# HW1_Justin_Ngo_u0453732_MotorPCB.net
KiCad netlist of a schematic drawn in EAGLE
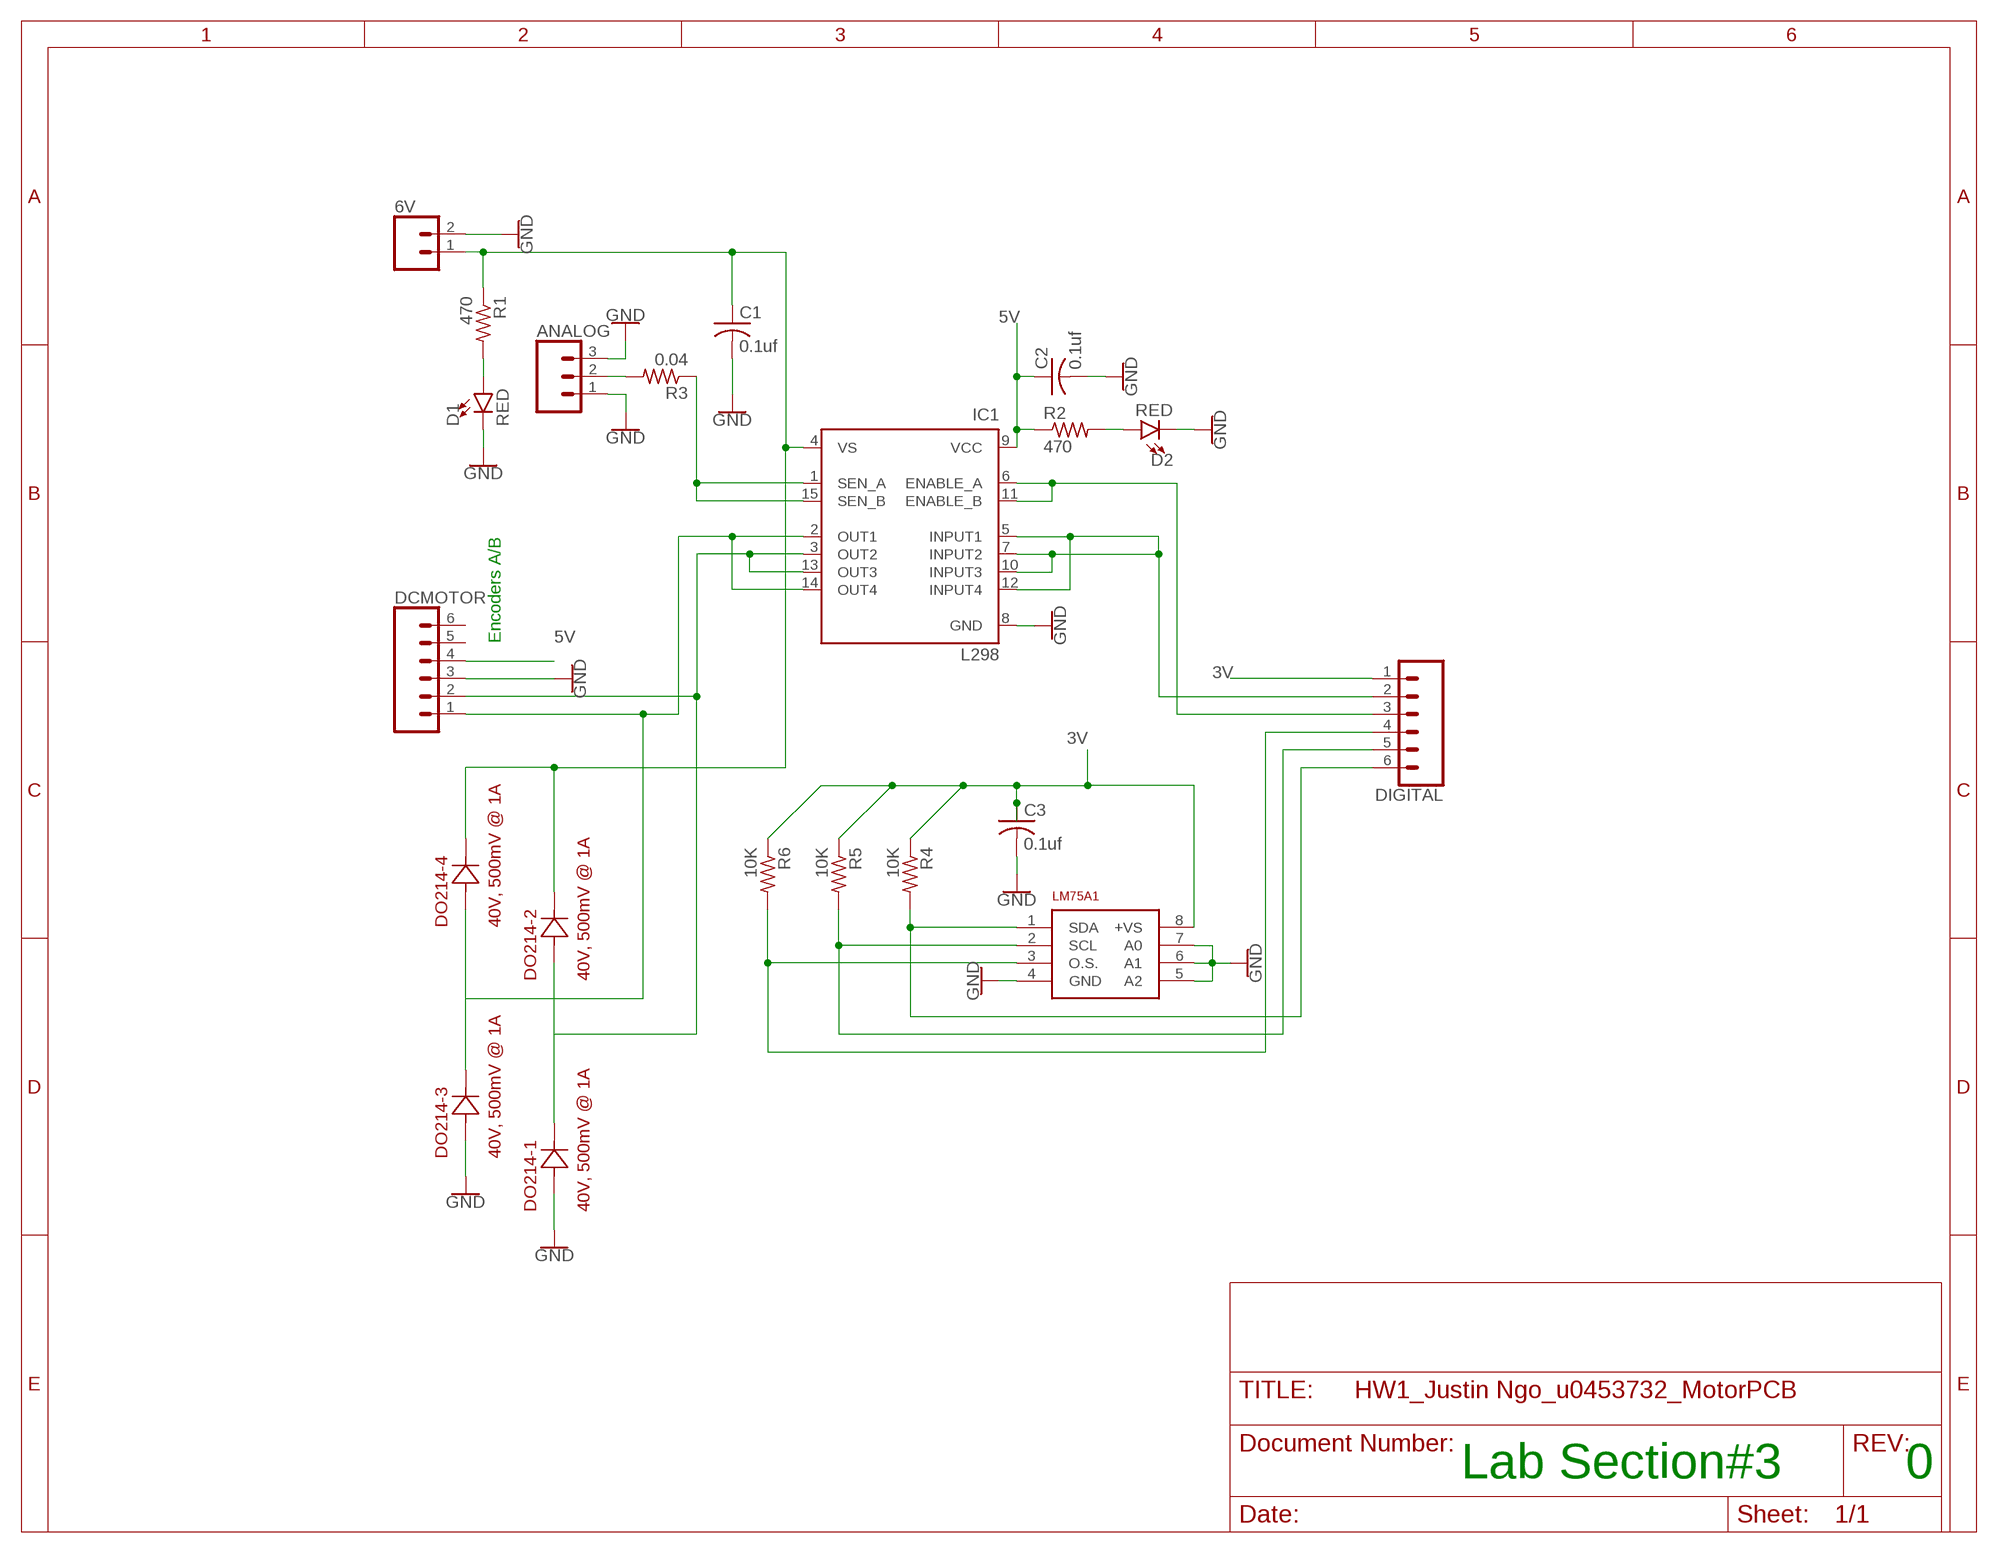
[diagram p0: schematic, sheet 1]

(export (version "E")
  (design (tool "Eeschema 10.0.6"))
  (components
    (comp (ref "6V")
      (value "CONN_025MM")
      (footprint "eagle-import:SCREWTERMINAL-5MM-2")
      (libsource (lib "eagle-import") (part "CONN_025MM"))
    )
    (comp (ref "ANALOG")
      (value "CONN_03")
      (footprint "eagle-import:1X03")
      (libsource (lib "eagle-import") (part "CONN_03"))
    )
    (comp (ref "C1")
      (value "0.1uf")
      (footprint "eagle-import:C1206")
      (libsource (lib "eagle-import") (part "C-USC1206"))
    )
    (comp (ref "C2")
      (value "0.1uf")
      (footprint "eagle-import:C1206")
      (libsource (lib "eagle-import") (part "C-USC1206"))
    )
    (comp (ref "C3")
      (value "0.1uf")
      (footprint "eagle-import:C1206")
      (libsource (lib "eagle-import") (part "C-USC1206"))
    )
    (comp (ref "D1")
      (value "RED")
      (footprint "eagle-import:LED-1206")
      (libsource (lib "eagle-import") (part "LED-RED1206"))
    )
    (comp (ref "D2")
      (value "RED")
      (footprint "eagle-import:LED-1206")
      (libsource (lib "eagle-import") (part "LED-RED1206"))
    )
    (comp (ref "DCMOTOR")
      (value "CONN_06LOCK_LONGPADS")
      (footprint "eagle-import:1X06_LOCK_LONGPADS")
      (libsource (lib "eagle-import") (part "CONN_06LOCK_LONGPADS"))
    )
    (comp (ref "DIGITAL")
      (value "CONN_06LOCK_LONGPADS")
      (footprint "eagle-import:1X06_LOCK_LONGPADS")
      (libsource (lib "eagle-import") (part "CONN_06LOCK_LONGPADS"))
    )
    (comp (ref "DO214-1")
      (value "40V, 500mV @ 1A")
      (footprint "eagle-import:DIODE_DO214AC")
      (fields
        (field (name "MANUFACTURER_PART_NUMBER") "SS14")
        (field (name "RSPARTNUMBER") "4470352")
        (field (name "COPYRIGHT") "Copyright C 2015 Accelerated Designs. All rights reserved")
      )
      (libsource (lib "eagle-import") (part "SS14"))
    )
    (comp (ref "DO214-2")
      (value "40V, 500mV @ 1A")
      (footprint "eagle-import:DIODE_DO214AC")
      (fields
        (field (name "MANUFACTURER_PART_NUMBER") "SS14")
        (field (name "RSPARTNUMBER") "4470352")
        (field (name "COPYRIGHT") "Copyright C 2015 Accelerated Designs. All rights reserved")
      )
      (libsource (lib "eagle-import") (part "SS14"))
    )
    (comp (ref "DO214-3")
      (value "40V, 500mV @ 1A")
      (footprint "eagle-import:DIODE_DO214AC")
      (fields
        (field (name "MANUFACTURER_PART_NUMBER") "SS14")
        (field (name "RSPARTNUMBER") "4470352")
        (field (name "COPYRIGHT") "Copyright C 2015 Accelerated Designs. All rights reserved")
      )
      (libsource (lib "eagle-import") (part "SS14"))
    )
    (comp (ref "DO214-4")
      (value "40V, 500mV @ 1A")
      (footprint "eagle-import:DIODE_DO214AC")
      (fields
        (field (name "MANUFACTURER_PART_NUMBER") "SS14")
        (field (name "RSPARTNUMBER") "4470352")
        (field (name "COPYRIGHT") "Copyright C 2015 Accelerated Designs. All rights reserved")
      )
      (libsource (lib "eagle-import") (part "SS14"))
    )
    (comp (ref "IC1")
      (value "L298")
      (footprint "eagle-import:MULTIWATT-15")
      (fields (field (name "MPN") "L298N"))
      (libsource (lib "eagle-import") (part "L298"))
    )
    (comp (ref "LM75A1")
      (value "TI-LM75A")
      (footprint "eagle-import:TI-LM75A")
      (libsource (lib "eagle-import") (part "TI-LM75A"))
    )
    (comp (ref "R1")
      (value "470")
      (footprint "eagle-import:R1206")
      (libsource (lib "eagle-import") (part "R-US_R1206"))
    )
    (comp (ref "R2")
      (value "470")
      (footprint "eagle-import:R1206")
      (libsource (lib "eagle-import") (part "R-US_R1206"))
    )
    (comp (ref "R3")
      (value "0.04")
      (footprint "eagle-import:R1206")
      (libsource (lib "eagle-import") (part "R-US_R1206"))
    )
    (comp (ref "R4")
      (value "10K")
      (footprint "eagle-import:R1206")
      (libsource (lib "eagle-import") (part "R-US_R1206"))
    )
    (comp (ref "R5")
      (value "10K")
      (footprint "eagle-import:R1206")
      (libsource (lib "eagle-import") (part "R-US_R1206"))
    )
    (comp (ref "R6")
      (value "10K")
      (footprint "eagle-import:R1206")
      (libsource (lib "eagle-import") (part "R-US_R1206"))
    )
  )
  (nets
    (net (code "1") (name "/3V") (class "Default")
      (node (ref "C3") (pin "1") (pinfunction "1_1") (pintype "passive"))
      (node (ref "DIGITAL") (pin "1") (pinfunction "1_1") (pintype "passive"))
      (node (ref "LM75A1") (pin "8") (pinfunction "+VS_8") (pintype "bidirectional"))
      (node (ref "R4") (pin "1") (pinfunction "1_1") (pintype "passive"))
      (node (ref "R5") (pin "1") (pinfunction "1_1") (pintype "passive"))
      (node (ref "R6") (pin "1") (pinfunction "1_1") (pintype "passive"))
    )
    (net (code "2") (name "/5V") (class "Default")
      (node (ref "C2") (pin "1") (pinfunction "1_1") (pintype "passive"))
      (node (ref "DCMOTOR") (pin "4") (pinfunction "4_4") (pintype "passive"))
      (node (ref "IC1") (pin "9") (pinfunction "VCC_9") (pintype "power_in"))
      (node (ref "R2") (pin "1") (pinfunction "1_1") (pintype "passive"))
    )
    (net (code "3") (name "GND") (class "Default")
      (node (ref "6V") (pin "2") (pinfunction "2_2") (pintype "passive"))
      (node (ref "ANALOG") (pin "1") (pinfunction "1_1") (pintype "passive"))
      (node (ref "ANALOG") (pin "3") (pinfunction "3_3") (pintype "passive"))
      (node (ref "C1") (pin "2") (pinfunction "2_2") (pintype "passive"))
      (node (ref "C2") (pin "2") (pinfunction "2_2") (pintype "passive"))
      (node (ref "C3") (pin "2") (pinfunction "2_2") (pintype "passive"))
      (node (ref "D1") (pin "C") (pinfunction "C_C") (pintype "passive"))
      (node (ref "D2") (pin "C") (pinfunction "C_C") (pintype "passive"))
      (node (ref "DCMOTOR") (pin "3") (pinfunction "3_3") (pintype "passive"))
      (node (ref "DO214-1") (pin "2") (pinfunction "21_2") (pintype "passive"))
      (node (ref "DO214-3") (pin "2") (pinfunction "21_2") (pintype "passive"))
      (node (ref "IC1") (pin "8") (pinfunction "GND_8") (pintype "power_in"))
      (node (ref "LM75A1") (pin "4") (pinfunction "GND_4") (pintype "bidirectional"))
      (node (ref "LM75A1") (pin "5") (pinfunction "A2_5") (pintype "bidirectional"))
      (node (ref "LM75A1") (pin "6") (pinfunction "A1_6") (pintype "bidirectional"))
      (node (ref "LM75A1") (pin "7") (pinfunction "A0_7") (pintype "bidirectional"))
    )
    (net (code "4") (name "Net-(ANALOG-Pad2)") (class "Default")
      (node (ref "ANALOG") (pin "2") (pinfunction "2_2") (pintype "passive"))
      (node (ref "R3") (pin "2") (pinfunction "2_2") (pintype "passive"))
    )
    (net (code "5") (name "Net-(D1-PadA)") (class "Default")
      (node (ref "D1") (pin "A") (pinfunction "A_A") (pintype "passive"))
      (node (ref "R1") (pin "2") (pinfunction "2_2") (pintype "passive"))
    )
    (net (code "6") (name "Net-(D2-PadA)") (class "Default")
      (node (ref "D2") (pin "A") (pinfunction "A_A") (pintype "passive"))
      (node (ref "R2") (pin "2") (pinfunction "2_2") (pintype "passive"))
    )
    (net (code "7") (name "Net-(DO214-1-12)") (class "Default")
      (node (ref "DCMOTOR") (pin "2") (pinfunction "2_2") (pintype "passive"))
      (node (ref "DO214-1") (pin "1") (pinfunction "12_1") (pintype "passive"))
      (node (ref "DO214-2") (pin "2") (pinfunction "21_2") (pintype "passive"))
      (node (ref "IC1") (pin "13") (pinfunction "OUT3_13") (pintype "output"))
      (node (ref "IC1") (pin "3") (pinfunction "OUT2_3") (pintype "output"))
    )
    (net (code "8") (name "Net-(DO214-2-12)") (class "Default")
      (node (ref "6V") (pin "1") (pinfunction "1_1") (pintype "passive"))
      (node (ref "C1") (pin "1") (pinfunction "1_1") (pintype "passive"))
      (node (ref "DO214-2") (pin "1") (pinfunction "12_1") (pintype "passive"))
      (node (ref "DO214-4") (pin "1") (pinfunction "12_1") (pintype "passive"))
      (node (ref "IC1") (pin "4") (pinfunction "VS_4") (pintype "power_in"))
      (node (ref "R1") (pin "1") (pinfunction "1_1") (pintype "passive"))
    )
    (net (code "9") (name "Net-(DO214-3-12)") (class "Default")
      (node (ref "DCMOTOR") (pin "1") (pinfunction "1_1") (pintype "passive"))
      (node (ref "DO214-3") (pin "1") (pinfunction "12_1") (pintype "passive"))
      (node (ref "DO214-4") (pin "2") (pinfunction "21_2") (pintype "passive"))
      (node (ref "IC1") (pin "14") (pinfunction "OUT4_14") (pintype "output"))
      (node (ref "IC1") (pin "2") (pinfunction "OUT1_2") (pintype "output"))
    )
    (net (code "10") (name "Net-(IC1-ENABLE_A)") (class "Default")
      (node (ref "DIGITAL") (pin "3") (pinfunction "3_3") (pintype "passive"))
      (node (ref "IC1") (pin "11") (pinfunction "ENABLE_B_11") (pintype "input"))
      (node (ref "IC1") (pin "6") (pinfunction "ENABLE_A_6") (pintype "input"))
    )
    (net (code "11") (name "Net-(IC1-INPUT1)") (class "Default")
      (node (ref "DIGITAL") (pin "2") (pinfunction "2_2") (pintype "passive"))
      (node (ref "IC1") (pin "10") (pinfunction "INPUT3_10") (pintype "input"))
      (node (ref "IC1") (pin "12") (pinfunction "INPUT4_12") (pintype "input"))
      (node (ref "IC1") (pin "5") (pinfunction "INPUT1_5") (pintype "input"))
      (node (ref "IC1") (pin "7") (pinfunction "INPUT2_7") (pintype "input"))
    )
    (net (code "12") (name "Net-(IC1-SEN_A)") (class "Default")
      (node (ref "IC1") (pin "1") (pinfunction "SEN_A_1") (pintype "input"))
      (node (ref "IC1") (pin "15") (pinfunction "SEN_B_15") (pintype "input"))
      (node (ref "R3") (pin "1") (pinfunction "1_1") (pintype "passive"))
    )
    (net (code "13") (name "Net-(LM75A1-O.S.)") (class "Default")
      (node (ref "DIGITAL") (pin "4") (pinfunction "4_4") (pintype "passive"))
      (node (ref "LM75A1") (pin "3") (pinfunction "O.S._3") (pintype "bidirectional"))
      (node (ref "R6") (pin "2") (pinfunction "2_2") (pintype "passive"))
    )
    (net (code "14") (name "Net-(LM75A1-SCL)") (class "Default")
      (node (ref "DIGITAL") (pin "5") (pinfunction "5_5") (pintype "passive"))
      (node (ref "LM75A1") (pin "2") (pinfunction "SCL_2") (pintype "bidirectional"))
      (node (ref "R5") (pin "2") (pinfunction "2_2") (pintype "passive"))
    )
    (net (code "15") (name "Net-(LM75A1-SDA)") (class "Default")
      (node (ref "DIGITAL") (pin "6") (pinfunction "6_6") (pintype "passive"))
      (node (ref "LM75A1") (pin "1") (pinfunction "SDA_1") (pintype "bidirectional"))
      (node (ref "R4") (pin "2") (pinfunction "2_2") (pintype "passive"))
    )
    (net (code "16") (name "unconnected-(DCMOTOR-Pad5)") (class "Default")
      (node (ref "DCMOTOR") (pin "5") (pinfunction "5_5") (pintype "passive"))
    )
    (net (code "17") (name "unconnected-(DCMOTOR-Pad6)") (class "Default")
      (node (ref "DCMOTOR") (pin "6") (pinfunction "6_6") (pintype "passive"))
    )
  )
)
